# armBandShield.net
KiCad netlist of a schematic drawn in EAGLE
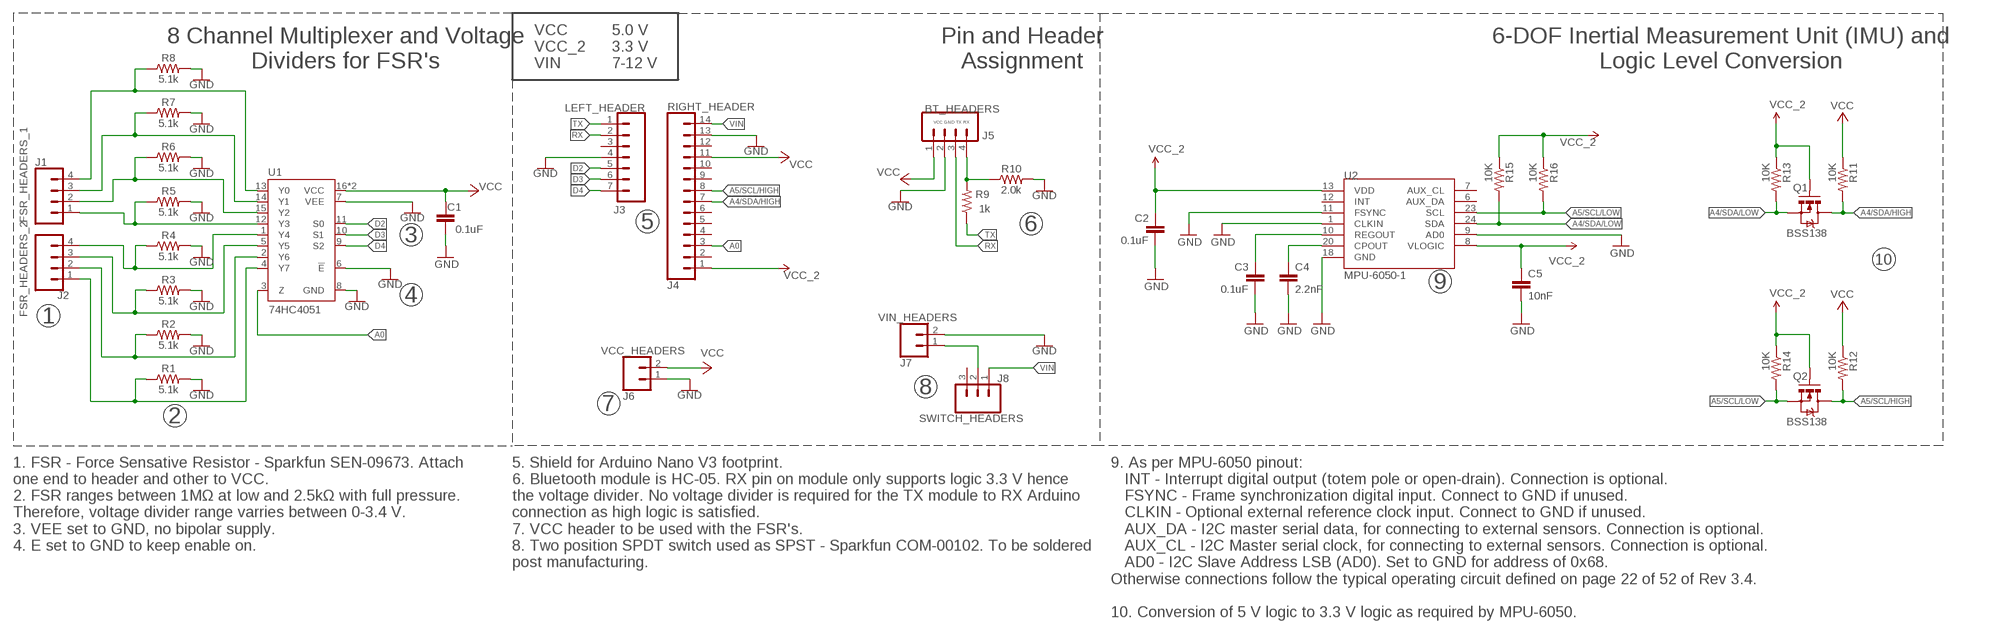
[diagram p0: schematic, sheet 1]

(export (version "E")
  (design (tool "Eeschema 10.0.6"))
  (components
    (comp (ref "74HC4051")
      (value "U1")
      (footprint "eagle-import:DHVQFN-16-2.5X3.5MM")
      (libsource (lib "eagle-import") (part "744051BQHC"))
    )
    (comp (ref "BT_HEADERS")
      (value "J5")
      (footprint "eagle-import:1X04")
      (libsource (lib "eagle-import") (part "CONN_04"))
    )
    (comp (ref "C1")
      (value "0.1uF")
      (footprint "eagle-import:0603-CAP")
      (libsource (lib "eagle-import") (part "0.1UF-25V(+80/-20%)(0603)"))
    )
    (comp (ref "C2")
      (value "0.1uF")
      (footprint "eagle-import:0603-CAP")
      (libsource (lib "eagle-import") (part "0.1UF-25V(+80/-20%)(0603)"))
    )
    (comp (ref "C3")
      (value "0.1uF")
      (footprint "eagle-import:0603-CAP")
      (libsource (lib "eagle-import") (part "0.1UF-25V(+80/-20%)(0603)"))
    )
    (comp (ref "C4")
      (value "2.2nF")
      (footprint "eagle-import:0603")
      (libsource (lib "eagle-import") (part "2.2NF/2200PF-0603-50V-10%"))
    )
    (comp (ref "C5")
      (value "10nF")
      (footprint "eagle-import:0603")
      (libsource (lib "eagle-import") (part "10NF-0603-50V-10%"))
    )
    (comp (ref "J1")
      (value "FSR_HEADERS_1")
      (footprint "eagle-import:1X04")
      (libsource (lib "eagle-import") (part "CONN_04"))
    )
    (comp (ref "J2")
      (value "FSR_HEADERS_2")
      (footprint "eagle-import:1X04")
      (libsource (lib "eagle-import") (part "CONN_04"))
    )
    (comp (ref "LEFT_HEADER")
      (value "J3")
      (footprint "eagle-import:1X07")
      (libsource (lib "eagle-import") (part "CONN_07"))
    )
    (comp (ref "Q1")
      (value "BSS138")
      (footprint "eagle-import:SOT23-3")
      (libsource (lib "eagle-import") (part "MOSFET-NCHANNELSMD"))
    )
    (comp (ref "Q2")
      (value "BSS138")
      (footprint "eagle-import:SOT23-3")
      (libsource (lib "eagle-import") (part "MOSFET-NCHANNELSMD"))
    )
    (comp (ref "R1")
      (value "5.1k")
      (footprint "eagle-import:0603")
      (libsource (lib "eagle-import") (part "5.1KOHM5.1KOHM-0603-1/10W-1%"))
    )
    (comp (ref "R2")
      (value "5.1k")
      (footprint "eagle-import:0603")
      (libsource (lib "eagle-import") (part "5.1KOHM5.1KOHM-0603-1/10W-1%"))
    )
    (comp (ref "R3")
      (value "5.1k")
      (footprint "eagle-import:0603")
      (libsource (lib "eagle-import") (part "5.1KOHM5.1KOHM-0603-1/10W-1%"))
    )
    (comp (ref "R4")
      (value "5.1k")
      (footprint "eagle-import:0603")
      (libsource (lib "eagle-import") (part "5.1KOHM5.1KOHM-0603-1/10W-1%"))
    )
    (comp (ref "R5")
      (value "5.1k")
      (footprint "eagle-import:0603")
      (libsource (lib "eagle-import") (part "5.1KOHM5.1KOHM-0603-1/10W-1%"))
    )
    (comp (ref "R6")
      (value "5.1k")
      (footprint "eagle-import:0603")
      (libsource (lib "eagle-import") (part "5.1KOHM5.1KOHM-0603-1/10W-1%"))
    )
    (comp (ref "R7")
      (value "5.1k")
      (footprint "eagle-import:0603")
      (libsource (lib "eagle-import") (part "5.1KOHM5.1KOHM-0603-1/10W-1%"))
    )
    (comp (ref "R8")
      (value "5.1k")
      (footprint "eagle-import:0603")
      (libsource (lib "eagle-import") (part "5.1KOHM5.1KOHM-0603-1/10W-1%"))
    )
    (comp (ref "R9")
      (value "1k")
      (footprint "eagle-import:0603")
      (libsource (lib "eagle-import") (part "1KOHM-0603-1/10W-1%"))
    )
    (comp (ref "R10")
      (value "2.0k")
      (footprint "eagle-import:0603")
      (libsource (lib "eagle-import") (part "2.0KOHM-0603-1/10W-5%"))
    )
    (comp (ref "R11")
      (value "10K")
      (footprint "eagle-import:0603-RES")
      (libsource (lib "eagle-import") (part "RESISTOR0603-RES"))
    )
    (comp (ref "R12")
      (value "10K")
      (footprint "eagle-import:0603-RES")
      (libsource (lib "eagle-import") (part "RESISTOR0603-RES"))
    )
    (comp (ref "R13")
      (value "10K")
      (footprint "eagle-import:0603-RES")
      (libsource (lib "eagle-import") (part "RESISTOR0603-RES"))
    )
    (comp (ref "R14")
      (value "10K")
      (footprint "eagle-import:0603-RES")
      (libsource (lib "eagle-import") (part "RESISTOR0603-RES"))
    )
    (comp (ref "R15")
      (value "10K")
      (footprint "eagle-import:0603-RES")
      (libsource (lib "eagle-import") (part "10KOHM-1/10W-1%(0603)0603"))
    )
    (comp (ref "R16")
      (value "10K")
      (footprint "eagle-import:0603-RES")
      (libsource (lib "eagle-import") (part "10KOHM-1/10W-1%(0603)0603"))
    )
    (comp (ref "RIGHT_HEADER")
      (value "J4")
      (footprint "eagle-import:1X14")
      (libsource (lib "eagle-import") (part "CONN_14"))
    )
    (comp (ref "SWITCH_HEADERS")
      (value "J8")
      (footprint "eagle-import:1X03")
      (libsource (lib "eagle-import") (part "CONN_03"))
    )
    (comp (ref "U2")
      (value "MPU-6050-1")
      (footprint "eagle-import:QFN-24-4MM2")
      (libsource (lib "eagle-import") (part "MPU-6050-1"))
    )
    (comp (ref "VCC_HEADERS")
      (value "J6")
      (footprint "eagle-import:1X02_LONGPADS")
      (libsource (lib "eagle-import") (part "CONN_02PTH3"))
    )
    (comp (ref "VIN_HEADERS")
      (value "J7")
      (footprint "eagle-import:1X02_LONGPADS")
      (libsource (lib "eagle-import") (part "CONN_02PTH3"))
    )
  )
  (nets
    (net (code "1") (name "A0") (class "Default")
      (node (ref "74HC4051") (pin "3") (pinfunction "Z_3") (pintype "bidirectional"))
      (node (ref "RIGHT_HEADER") (pin "3") (pinfunction "3_3") (pintype "passive"))
    )
    (net (code "2") (name "A4{slash}SDA{slash}HIGH") (class "Default")
      (node (ref "Q1") (pin "3") (pinfunction "D_3") (pintype "passive"))
      (node (ref "R11") (pin "2") (pinfunction "2_2") (pintype "passive"))
      (node (ref "RIGHT_HEADER") (pin "7") (pinfunction "7_7") (pintype "passive"))
    )
    (net (code "3") (name "A4{slash}SDA{slash}LOW") (class "Default")
      (node (ref "Q1") (pin "2") (pinfunction "S_2") (pintype "passive"))
      (node (ref "R13") (pin "2") (pinfunction "2_2") (pintype "passive"))
      (node (ref "R15") (pin "2") (pinfunction "2_2") (pintype "passive"))
      (node (ref "U2") (pin "24") (pinfunction "SDA_24") (pintype "bidirectional"))
    )
    (net (code "4") (name "A5{slash}SCL{slash}HIGH") (class "Default")
      (node (ref "Q2") (pin "3") (pinfunction "D_3") (pintype "passive"))
      (node (ref "R12") (pin "2") (pinfunction "2_2") (pintype "passive"))
      (node (ref "RIGHT_HEADER") (pin "8") (pinfunction "8_8") (pintype "passive"))
    )
    (net (code "5") (name "A5{slash}SCL{slash}LOW") (class "Default")
      (node (ref "Q2") (pin "2") (pinfunction "S_2") (pintype "passive"))
      (node (ref "R14") (pin "2") (pinfunction "2_2") (pintype "passive"))
      (node (ref "R16") (pin "2") (pinfunction "2_2") (pintype "passive"))
      (node (ref "U2") (pin "23") (pinfunction "SCL_23") (pintype "bidirectional"))
    )
    (net (code "6") (name "D2") (class "Default")
      (node (ref "74HC4051") (pin "11") (pinfunction "S0_11") (pintype "bidirectional"))
      (node (ref "LEFT_HEADER") (pin "5") (pinfunction "5_5") (pintype "passive"))
    )
    (net (code "7") (name "D3") (class "Default")
      (node (ref "74HC4051") (pin "10") (pinfunction "S1_10") (pintype "bidirectional"))
      (node (ref "LEFT_HEADER") (pin "6") (pinfunction "6_6") (pintype "passive"))
    )
    (net (code "8") (name "D4") (class "Default")
      (node (ref "74HC4051") (pin "9") (pinfunction "S2_9") (pintype "bidirectional"))
      (node (ref "LEFT_HEADER") (pin "7") (pinfunction "7_7") (pintype "passive"))
    )
    (net (code "9") (name "GND") (class "Default")
      (node (ref "74HC4051") (pin "6") (pinfunction "~{E}_6") (pintype "bidirectional"))
      (node (ref "74HC4051") (pin "7") (pinfunction "VEE_7") (pintype "bidirectional"))
      (node (ref "74HC4051") (pin "8") (pinfunction "GND_8") (pintype "bidirectional"))
      (node (ref "BT_HEADERS") (pin "2") (pinfunction "2_2") (pintype "passive"))
      (node (ref "C1") (pin "2") (pinfunction "2_2") (pintype "passive"))
      (node (ref "C2") (pin "2") (pinfunction "2_2") (pintype "passive"))
      (node (ref "C3") (pin "2") (pinfunction "2_2") (pintype "passive"))
      (node (ref "C4") (pin "2") (pinfunction "2_2") (pintype "passive"))
      (node (ref "C5") (pin "2") (pinfunction "2_2") (pintype "passive"))
      (node (ref "LEFT_HEADER") (pin "4") (pinfunction "4_4") (pintype "passive"))
      (node (ref "R1") (pin "2") (pinfunction "2_2") (pintype "passive"))
      (node (ref "R10") (pin "2") (pinfunction "2_2") (pintype "passive"))
      (node (ref "R2") (pin "2") (pinfunction "2_2") (pintype "passive"))
      (node (ref "R3") (pin "2") (pinfunction "2_2") (pintype "passive"))
      (node (ref "R4") (pin "2") (pinfunction "2_2") (pintype "passive"))
      (node (ref "R5") (pin "2") (pinfunction "2_2") (pintype "passive"))
      (node (ref "R6") (pin "2") (pinfunction "2_2") (pintype "passive"))
      (node (ref "R7") (pin "2") (pinfunction "2_2") (pintype "passive"))
      (node (ref "R8") (pin "2") (pinfunction "2_2") (pintype "passive"))
      (node (ref "RIGHT_HEADER") (pin "13") (pinfunction "13_13") (pintype "passive"))
      (node (ref "U2") (pin "1") (pinfunction "CLKIN_1") (pintype "bidirectional"))
      (node (ref "U2") (pin "11") (pinfunction "FSYNC_11") (pintype "bidirectional"))
      (node (ref "U2") (pin "18") (pinfunction "GND_18") (pintype "bidirectional"))
      (node (ref "U2") (pin "9") (pinfunction "AD0_9") (pintype "bidirectional"))
      (node (ref "VCC_HEADERS") (pin "1") (pinfunction "1_1") (pintype "passive"))
      (node (ref "VIN_HEADERS") (pin "2") (pinfunction "2_2") (pintype "passive"))
    )
    (net (code "10") (name "Net-(74HC4051-Y0)") (class "Default")
      (node (ref "74HC4051") (pin "13") (pinfunction "Y0_13") (pintype "bidirectional"))
      (node (ref "J1") (pin "4") (pinfunction "4_4") (pintype "passive"))
      (node (ref "R8") (pin "1") (pinfunction "1_1") (pintype "passive"))
    )
    (net (code "11") (name "Net-(74HC4051-Y1)") (class "Default")
      (node (ref "74HC4051") (pin "14") (pinfunction "Y1_14") (pintype "bidirectional"))
      (node (ref "J1") (pin "3") (pinfunction "3_3") (pintype "passive"))
      (node (ref "R7") (pin "1") (pinfunction "1_1") (pintype "passive"))
    )
    (net (code "12") (name "Net-(74HC4051-Y2)") (class "Default")
      (node (ref "74HC4051") (pin "15") (pinfunction "Y2_15") (pintype "bidirectional"))
      (node (ref "J1") (pin "2") (pinfunction "2_2") (pintype "passive"))
      (node (ref "R6") (pin "1") (pinfunction "1_1") (pintype "passive"))
    )
    (net (code "13") (name "Net-(74HC4051-Y3)") (class "Default")
      (node (ref "74HC4051") (pin "12") (pinfunction "Y3_12") (pintype "bidirectional"))
      (node (ref "J1") (pin "1") (pinfunction "1_1") (pintype "passive"))
      (node (ref "R5") (pin "1") (pinfunction "1_1") (pintype "passive"))
    )
    (net (code "14") (name "Net-(74HC4051-Y4)") (class "Default")
      (node (ref "74HC4051") (pin "1") (pinfunction "Y4_1") (pintype "bidirectional"))
      (node (ref "J2") (pin "4") (pinfunction "4_4") (pintype "passive"))
      (node (ref "R4") (pin "1") (pinfunction "1_1") (pintype "passive"))
    )
    (net (code "15") (name "Net-(74HC4051-Y5)") (class "Default")
      (node (ref "74HC4051") (pin "5") (pinfunction "Y5_5") (pintype "bidirectional"))
      (node (ref "J2") (pin "3") (pinfunction "3_3") (pintype "passive"))
      (node (ref "R3") (pin "1") (pinfunction "1_1") (pintype "passive"))
    )
    (net (code "16") (name "Net-(74HC4051-Y6)") (class "Default")
      (node (ref "74HC4051") (pin "2") (pinfunction "Y6_2") (pintype "bidirectional"))
      (node (ref "J2") (pin "2") (pinfunction "2_2") (pintype "passive"))
      (node (ref "R2") (pin "1") (pinfunction "1_1") (pintype "passive"))
    )
    (net (code "17") (name "Net-(74HC4051-Y7)") (class "Default")
      (node (ref "74HC4051") (pin "4") (pinfunction "Y7_4") (pintype "bidirectional"))
      (node (ref "J2") (pin "1") (pinfunction "1_1") (pintype "passive"))
      (node (ref "R1") (pin "1") (pinfunction "1_1") (pintype "passive"))
    )
    (net (code "18") (name "Net-(BT_HEADERS-Pad4)") (class "Default")
      (node (ref "BT_HEADERS") (pin "4") (pinfunction "4_4") (pintype "passive"))
      (node (ref "R10") (pin "1") (pinfunction "1_1") (pintype "passive"))
      (node (ref "R9") (pin "2") (pinfunction "2_2") (pintype "passive"))
    )
    (net (code "19") (name "Net-(SWITCH_HEADERS-Pad2)") (class "Default")
      (node (ref "SWITCH_HEADERS") (pin "2") (pinfunction "2_2") (pintype "passive"))
      (node (ref "VIN_HEADERS") (pin "1") (pinfunction "1_1") (pintype "passive"))
    )
    (net (code "20") (name "Net-(U2-CPOUT)") (class "Default")
      (node (ref "C4") (pin "1") (pinfunction "1_1") (pintype "passive"))
      (node (ref "U2") (pin "20") (pinfunction "CPOUT_20") (pintype "bidirectional"))
    )
    (net (code "21") (name "Net-(U2-REGOUT)") (class "Default")
      (node (ref "C3") (pin "1") (pinfunction "1_1") (pintype "passive"))
      (node (ref "U2") (pin "10") (pinfunction "REGOUT_10") (pintype "bidirectional"))
    )
    (net (code "22") (name "RX") (class "Default")
      (node (ref "BT_HEADERS") (pin "3") (pinfunction "3_3") (pintype "passive"))
      (node (ref "LEFT_HEADER") (pin "2") (pinfunction "2_2") (pintype "passive"))
    )
    (net (code "23") (name "TX") (class "Default")
      (node (ref "LEFT_HEADER") (pin "1") (pinfunction "1_1") (pintype "passive"))
      (node (ref "R9") (pin "1") (pinfunction "1_1") (pintype "passive"))
    )
    (net (code "24") (name "VCC") (class "Default")
      (node (ref "74HC4051") (pin "16") (pinfunction "VCC_16") (pintype "bidirectional"))
      (node (ref "74HC4051") (pin "EP") (pinfunction "VCC_EP") (pintype "bidirectional"))
      (node (ref "BT_HEADERS") (pin "1") (pinfunction "1_1") (pintype "passive"))
      (node (ref "C1") (pin "1") (pinfunction "1_1") (pintype "passive"))
      (node (ref "R11") (pin "1") (pinfunction "1_1") (pintype "passive"))
      (node (ref "R12") (pin "1") (pinfunction "1_1") (pintype "passive"))
      (node (ref "RIGHT_HEADER") (pin "11") (pinfunction "11_11") (pintype "passive"))
      (node (ref "VCC_HEADERS") (pin "2") (pinfunction "2_2") (pintype "passive"))
    )
    (net (code "25") (name "VCC_2") (class "Default")
      (node (ref "C2") (pin "1") (pinfunction "1_1") (pintype "passive"))
      (node (ref "C5") (pin "1") (pinfunction "1_1") (pintype "passive"))
      (node (ref "Q1") (pin "1") (pinfunction "G_1") (pintype "passive"))
      (node (ref "Q2") (pin "1") (pinfunction "G_1") (pintype "passive"))
      (node (ref "R13") (pin "1") (pinfunction "1_1") (pintype "passive"))
      (node (ref "R14") (pin "1") (pinfunction "1_1") (pintype "passive"))
      (node (ref "R15") (pin "1") (pinfunction "1_1") (pintype "passive"))
      (node (ref "R16") (pin "1") (pinfunction "1_1") (pintype "passive"))
      (node (ref "RIGHT_HEADER") (pin "1") (pinfunction "1_1") (pintype "passive"))
      (node (ref "U2") (pin "13") (pinfunction "VDD_13") (pintype "bidirectional"))
      (node (ref "U2") (pin "8") (pinfunction "VLOGIC_8") (pintype "bidirectional"))
    )
    (net (code "26") (name "VIN") (class "Default")
      (node (ref "RIGHT_HEADER") (pin "14") (pinfunction "14_14") (pintype "passive"))
      (node (ref "SWITCH_HEADERS") (pin "1") (pinfunction "1_1") (pintype "passive"))
    )
    (net (code "27") (name "unconnected-(LEFT_HEADER-Pad3)") (class "Default")
      (node (ref "LEFT_HEADER") (pin "3") (pinfunction "3_3") (pintype "passive"))
    )
    (net (code "28") (name "unconnected-(RIGHT_HEADER-Pad2)") (class "Default")
      (node (ref "RIGHT_HEADER") (pin "2") (pinfunction "2_2") (pintype "passive"))
    )
    (net (code "29") (name "unconnected-(RIGHT_HEADER-Pad4)") (class "Default")
      (node (ref "RIGHT_HEADER") (pin "4") (pinfunction "4_4") (pintype "passive"))
    )
    (net (code "30") (name "unconnected-(RIGHT_HEADER-Pad5)") (class "Default")
      (node (ref "RIGHT_HEADER") (pin "5") (pinfunction "5_5") (pintype "passive"))
    )
    (net (code "31") (name "unconnected-(RIGHT_HEADER-Pad6)") (class "Default")
      (node (ref "RIGHT_HEADER") (pin "6") (pinfunction "6_6") (pintype "passive"))
    )
    (net (code "32") (name "unconnected-(RIGHT_HEADER-Pad9)") (class "Default")
      (node (ref "RIGHT_HEADER") (pin "9") (pinfunction "9_9") (pintype "passive"))
    )
    (net (code "33") (name "unconnected-(RIGHT_HEADER-Pad10)") (class "Default")
      (node (ref "RIGHT_HEADER") (pin "10") (pinfunction "10_10") (pintype "passive"))
    )
    (net (code "34") (name "unconnected-(RIGHT_HEADER-Pad12)") (class "Default")
      (node (ref "RIGHT_HEADER") (pin "12") (pinfunction "12_12") (pintype "passive"))
    )
    (net (code "35") (name "unconnected-(SWITCH_HEADERS-Pad3)") (class "Default")
      (node (ref "SWITCH_HEADERS") (pin "3") (pinfunction "3_3") (pintype "passive"))
    )
    (net (code "36") (name "unconnected-(U2-AUX_CL-Pad7)") (class "Default")
      (node (ref "U2") (pin "7") (pinfunction "AUX_CL_7") (pintype "bidirectional"))
    )
    (net (code "37") (name "unconnected-(U2-AUX_DA-Pad6)") (class "Default")
      (node (ref "U2") (pin "6") (pinfunction "AUX_DA_6") (pintype "bidirectional"))
    )
    (net (code "38") (name "unconnected-(U2-INT-Pad12)") (class "Default")
      (node (ref "U2") (pin "12") (pinfunction "INT_12") (pintype "bidirectional"))
    )
  )
)
